# Stepper_control.net
KiCad netlist of a schematic drawn in Altium Designer
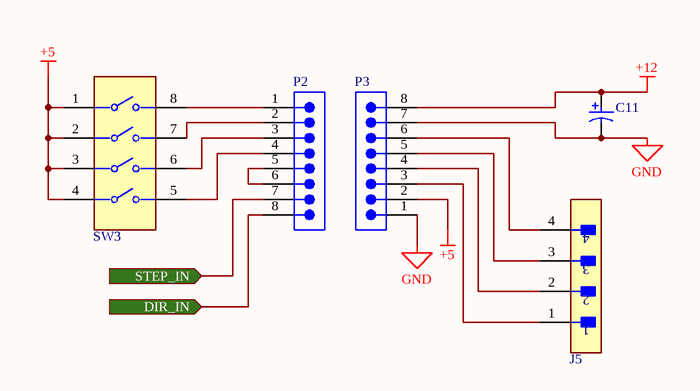
[diagram p0: Stepper_control.SchDoc]

(export (version "E")
  (design (tool "Eeschema 10.0.6"))
  (components
    (comp (ref "C11")
      (value "EEEFK1E101XP")
      (footprint "PNSC-FK-V-D8_V")
      (fields (field (name "MANUFACTURER") "Panasonic"))
      (libsource (lib "Altium Content Vault") (part "CAP-P-2"))
    )
    (comp (ref "J5")
      (value "B4B-XH-A(LF)(SN)")
      (footprint "FP-B4B-XH-A_LF_SN-MFG")
      (description "CONN HEADER VERT 4POS 2.5MM")
      (libsource (lib "Altium Content Vault") (part "299a8cea1bdcbc3624fe62c390fa72c"))
    )
    (comp (ref "P2")
      (value "61300811121")
      (footprint "61300811121")
      (libsource (lib "Altium Content Vault") (part "Header_Male_1R_08P"))
    )
    (comp (ref "P3")
      (value "61300811121")
      (footprint "61300811121")
      (libsource (lib "Altium Content Vault") (part "Header_Male_1R_08P"))
    )
    (comp (ref "SW3")
      (value "1825360-3")
      (footprint "FP-1825360-3-MFG")
      (description "SWITCH SLIDE DIP SPST 100MA 24V")
      (libsource (lib "Altium Content Vault") (part "8a6f13ad003845d0737bd9d25158ffb"))
    )
  )
  (nets
    (net (code "1") (name "+5") (class "Default")
      (node (ref "P3") (pin "2") (pinfunction "2_2") (pintype "passive"))
      (node (ref "SW3") (pin "1") (pinfunction "1_1") (pintype "passive"))
      (node (ref "SW3") (pin "2") (pinfunction "2_2") (pintype "passive"))
      (node (ref "SW3") (pin "3") (pinfunction "3_3") (pintype "passive"))
      (node (ref "SW3") (pin "4") (pinfunction "4_4") (pintype "passive"))
    )
    (net (code "2") (name "+12") (class "Default")
      (node (ref "C11") (pin "1") (pinfunction "1_1") (pintype "passive"))
      (node (ref "P3") (pin "8") (pinfunction "8_8") (pintype "passive"))
    )
    (net (code "3") (name "/DIR_IN") (class "Default")
      (node (ref "P2") (pin "8") (pinfunction "8_8") (pintype "passive"))
    )
    (net (code "4") (name "/STEP_IN") (class "Default")
      (node (ref "P2") (pin "7") (pinfunction "7_7") (pintype "passive"))
    )
    (net (code "5") (name "GND") (class "Default")
      (node (ref "C11") (pin "2") (pinfunction "2_2") (pintype "passive"))
      (node (ref "P3") (pin "1") (pinfunction "1_1") (pintype "passive"))
      (node (ref "P3") (pin "7") (pinfunction "7_7") (pintype "passive"))
    )
    (net (code "6") (name "Net-(J5-Pad1)") (class "Default")
      (node (ref "J5") (pin "1") (pinfunction "1_1") (pintype "passive"))
      (node (ref "P3") (pin "3") (pinfunction "3_3") (pintype "passive"))
    )
    (net (code "7") (name "Net-(J5-Pad2)") (class "Default")
      (node (ref "J5") (pin "2") (pinfunction "2_2") (pintype "passive"))
      (node (ref "P3") (pin "4") (pinfunction "4_4") (pintype "passive"))
    )
    (net (code "8") (name "Net-(J5-Pad3)") (class "Default")
      (node (ref "J5") (pin "3") (pinfunction "3_3") (pintype "passive"))
      (node (ref "P3") (pin "5") (pinfunction "5_5") (pintype "passive"))
    )
    (net (code "9") (name "Net-(J5-Pad4)") (class "Default")
      (node (ref "J5") (pin "4") (pinfunction "4_4") (pintype "passive"))
      (node (ref "P3") (pin "6") (pinfunction "6_6") (pintype "passive"))
    )
    (net (code "10") (name "Net-(P2-Pad1)") (class "Default")
      (node (ref "P2") (pin "1") (pinfunction "1_1") (pintype "passive"))
      (node (ref "SW3") (pin "8") (pinfunction "8_8") (pintype "passive"))
    )
    (net (code "11") (name "Net-(P2-Pad2)") (class "Default")
      (node (ref "P2") (pin "2") (pinfunction "2_2") (pintype "passive"))
      (node (ref "SW3") (pin "7") (pinfunction "7_7") (pintype "passive"))
    )
    (net (code "12") (name "Net-(P2-Pad3)") (class "Default")
      (node (ref "P2") (pin "3") (pinfunction "3_3") (pintype "passive"))
      (node (ref "SW3") (pin "6") (pinfunction "6_6") (pintype "passive"))
    )
    (net (code "13") (name "Net-(P2-Pad4)") (class "Default")
      (node (ref "P2") (pin "4") (pinfunction "4_4") (pintype "passive"))
      (node (ref "SW3") (pin "5") (pinfunction "5_5") (pintype "passive"))
    )
    (net (code "14") (name "Net-(P2-Pad5)") (class "Default")
      (node (ref "P2") (pin "5") (pinfunction "5_5") (pintype "passive"))
      (node (ref "P2") (pin "6") (pinfunction "6_6") (pintype "passive"))
    )
  )
)
